# Interface.net
KiCad netlist of a schematic drawn in Altium Designer
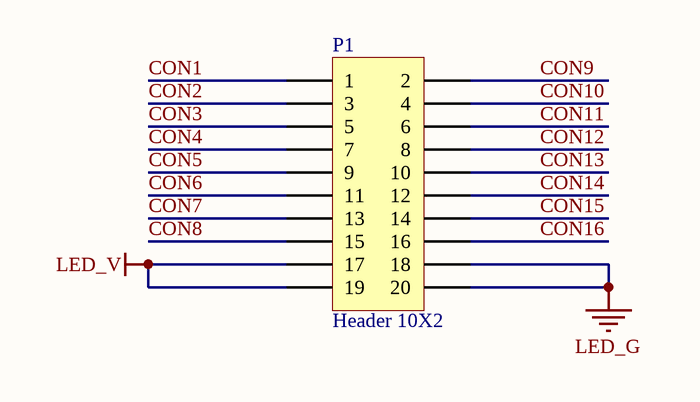
[diagram p0: Interface.SchDoc]

(export (version "E")
  (design (tool "Eeschema 10.0.6"))
  (components
    (comp (ref "P1")
      (value "Header 10X2")
      (footprint "HDR2.54-LI-2x10P")
      (description "Header, 10-Pin, Dual row")
      (fields (field (name "PUBLISHER") "Altium Limited"))
      (libsource (lib "Miscellaneous Connectors") (part "Header 10X2"))
    )
  )
  (nets
    (net (code "1") (name "/CON1") (class "Default")
      (node (ref "P1") (pin "1") (pinfunction "1_1") (pintype "passive"))
    )
    (net (code "2") (name "/CON2") (class "Default")
      (node (ref "P1") (pin "3") (pinfunction "3_3") (pintype "passive"))
    )
    (net (code "3") (name "/CON3") (class "Default")
      (node (ref "P1") (pin "5") (pinfunction "5_5") (pintype "passive"))
    )
    (net (code "4") (name "/CON4") (class "Default")
      (node (ref "P1") (pin "7") (pinfunction "7_7") (pintype "passive"))
    )
    (net (code "5") (name "/CON5") (class "Default")
      (node (ref "P1") (pin "9") (pinfunction "9_9") (pintype "passive"))
    )
    (net (code "6") (name "/CON6") (class "Default")
      (node (ref "P1") (pin "11") (pinfunction "11_11") (pintype "passive"))
    )
    (net (code "7") (name "/CON7") (class "Default")
      (node (ref "P1") (pin "13") (pinfunction "13_13") (pintype "passive"))
    )
    (net (code "8") (name "/CON8") (class "Default")
      (node (ref "P1") (pin "15") (pinfunction "15_15") (pintype "passive"))
    )
    (net (code "9") (name "/CON9") (class "Default")
      (node (ref "P1") (pin "2") (pinfunction "2_2") (pintype "passive"))
    )
    (net (code "10") (name "/CON10") (class "Default")
      (node (ref "P1") (pin "4") (pinfunction "4_4") (pintype "passive"))
    )
    (net (code "11") (name "/CON11") (class "Default")
      (node (ref "P1") (pin "6") (pinfunction "6_6") (pintype "passive"))
    )
    (net (code "12") (name "/CON12") (class "Default")
      (node (ref "P1") (pin "8") (pinfunction "8_8") (pintype "passive"))
    )
    (net (code "13") (name "/CON13") (class "Default")
      (node (ref "P1") (pin "10") (pinfunction "10_10") (pintype "passive"))
    )
    (net (code "14") (name "/CON14") (class "Default")
      (node (ref "P1") (pin "12") (pinfunction "12_12") (pintype "passive"))
    )
    (net (code "15") (name "/CON15") (class "Default")
      (node (ref "P1") (pin "14") (pinfunction "14_14") (pintype "passive"))
    )
    (net (code "16") (name "/CON16") (class "Default")
      (node (ref "P1") (pin "16") (pinfunction "16_16") (pintype "passive"))
    )
    (net (code "17") (name "LED_G") (class "Default")
      (node (ref "P1") (pin "18") (pinfunction "18_18") (pintype "passive"))
      (node (ref "P1") (pin "20") (pinfunction "20_20") (pintype "passive"))
    )
    (net (code "18") (name "LED_V") (class "Default")
      (node (ref "P1") (pin "17") (pinfunction "17_17") (pintype "passive"))
      (node (ref "P1") (pin "19") (pinfunction "19_19") (pintype "passive"))
    )
  )
)
